# Rectifire__PFC__Evaluation_Board.net
KiCad netlist of a schematic drawn in Altium Designer
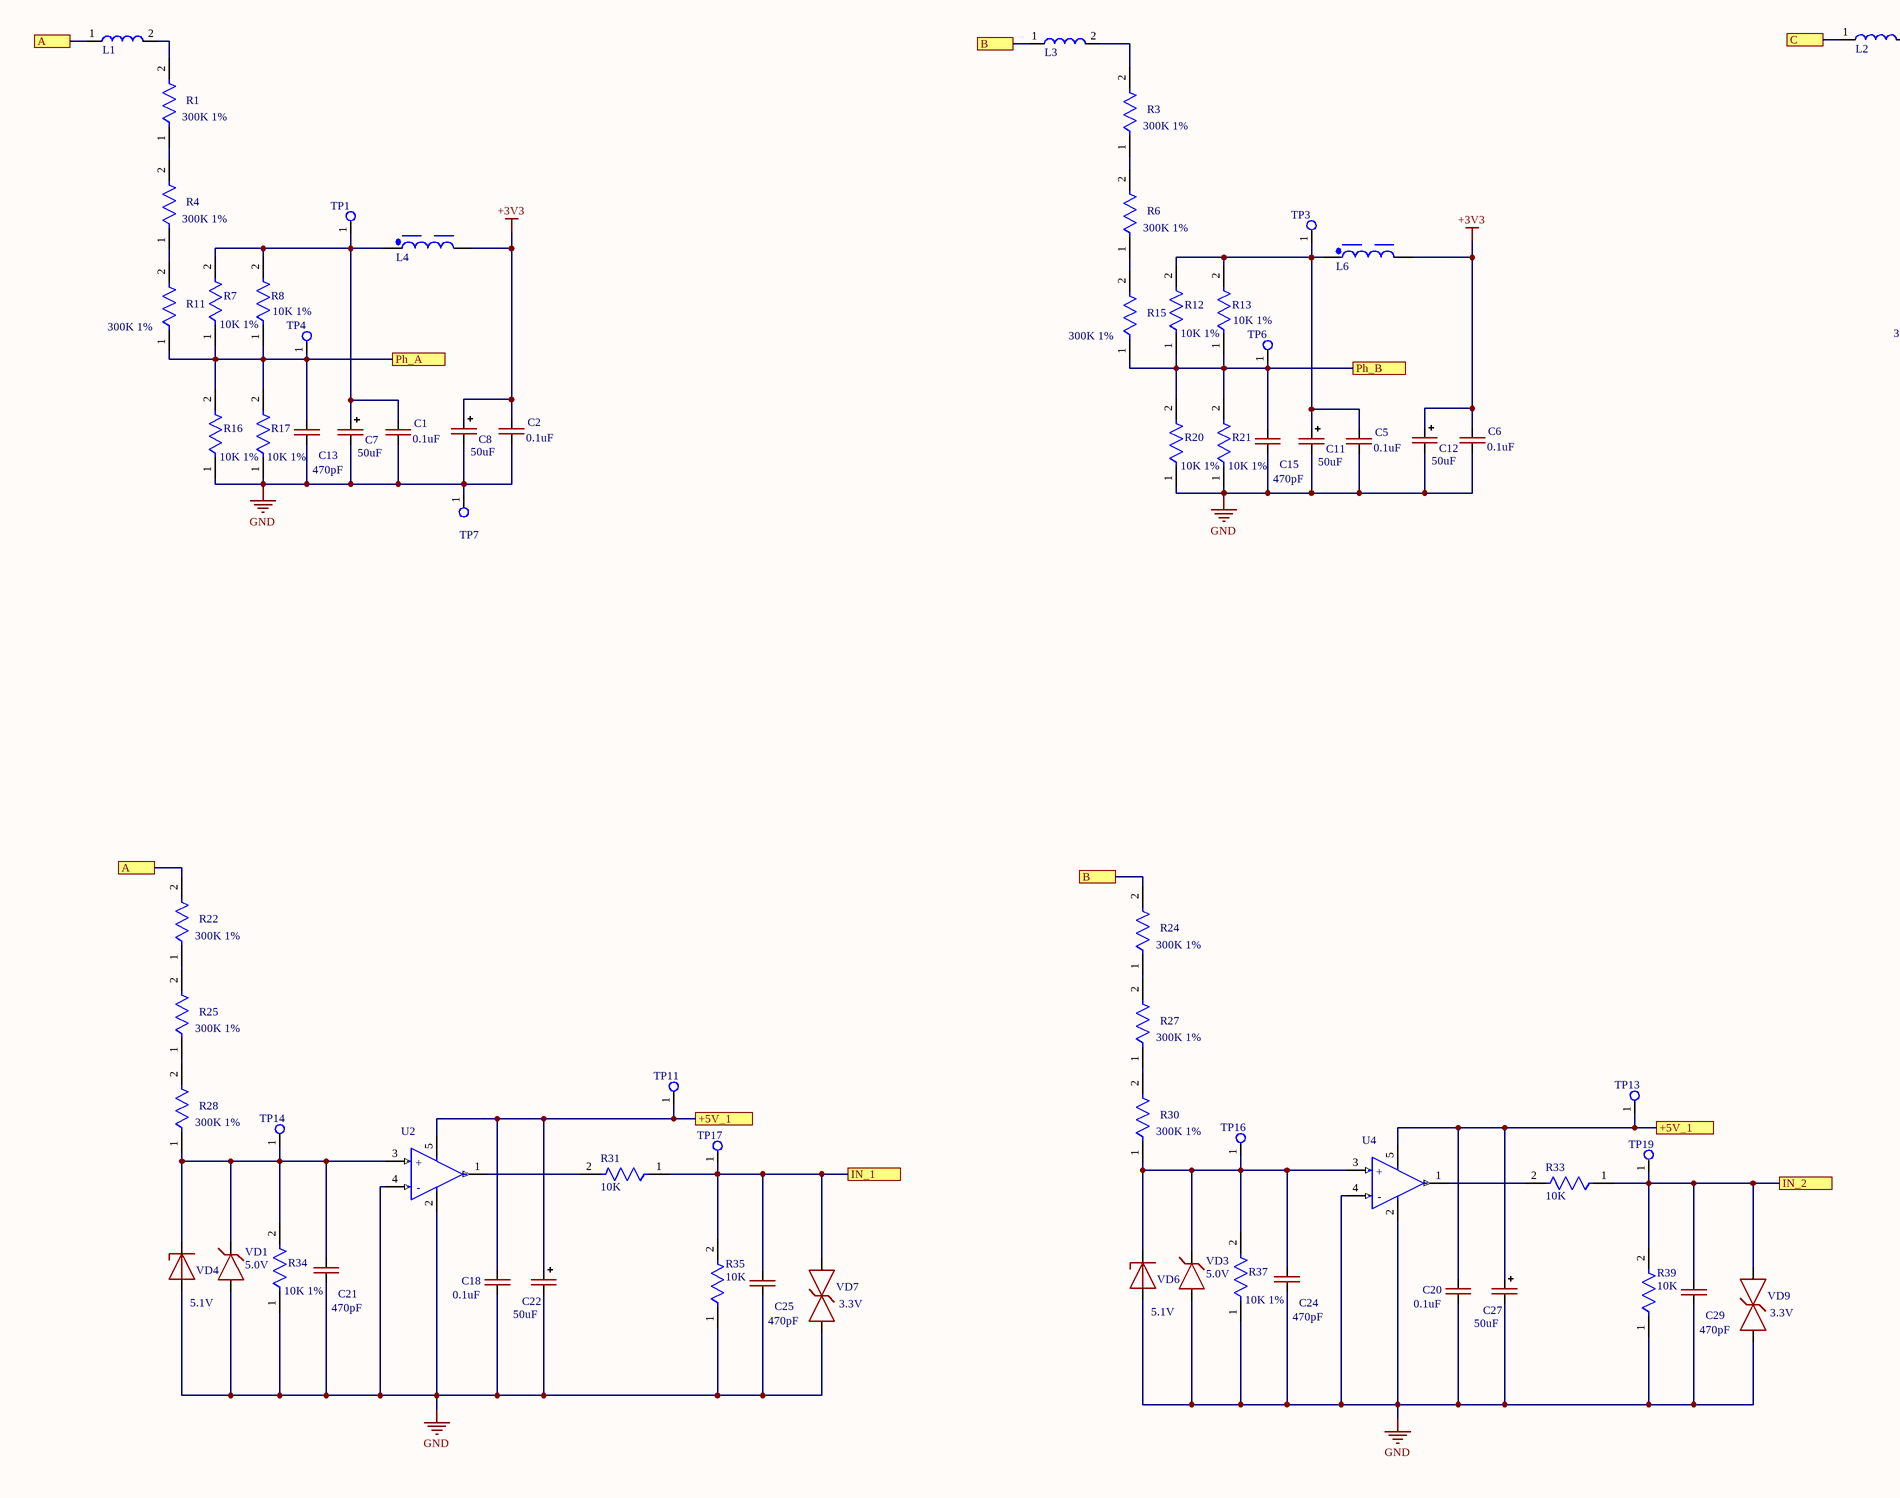
[diagram p0: Rectifire_(PFC)_Evaluation_Board.SchDoc, left]
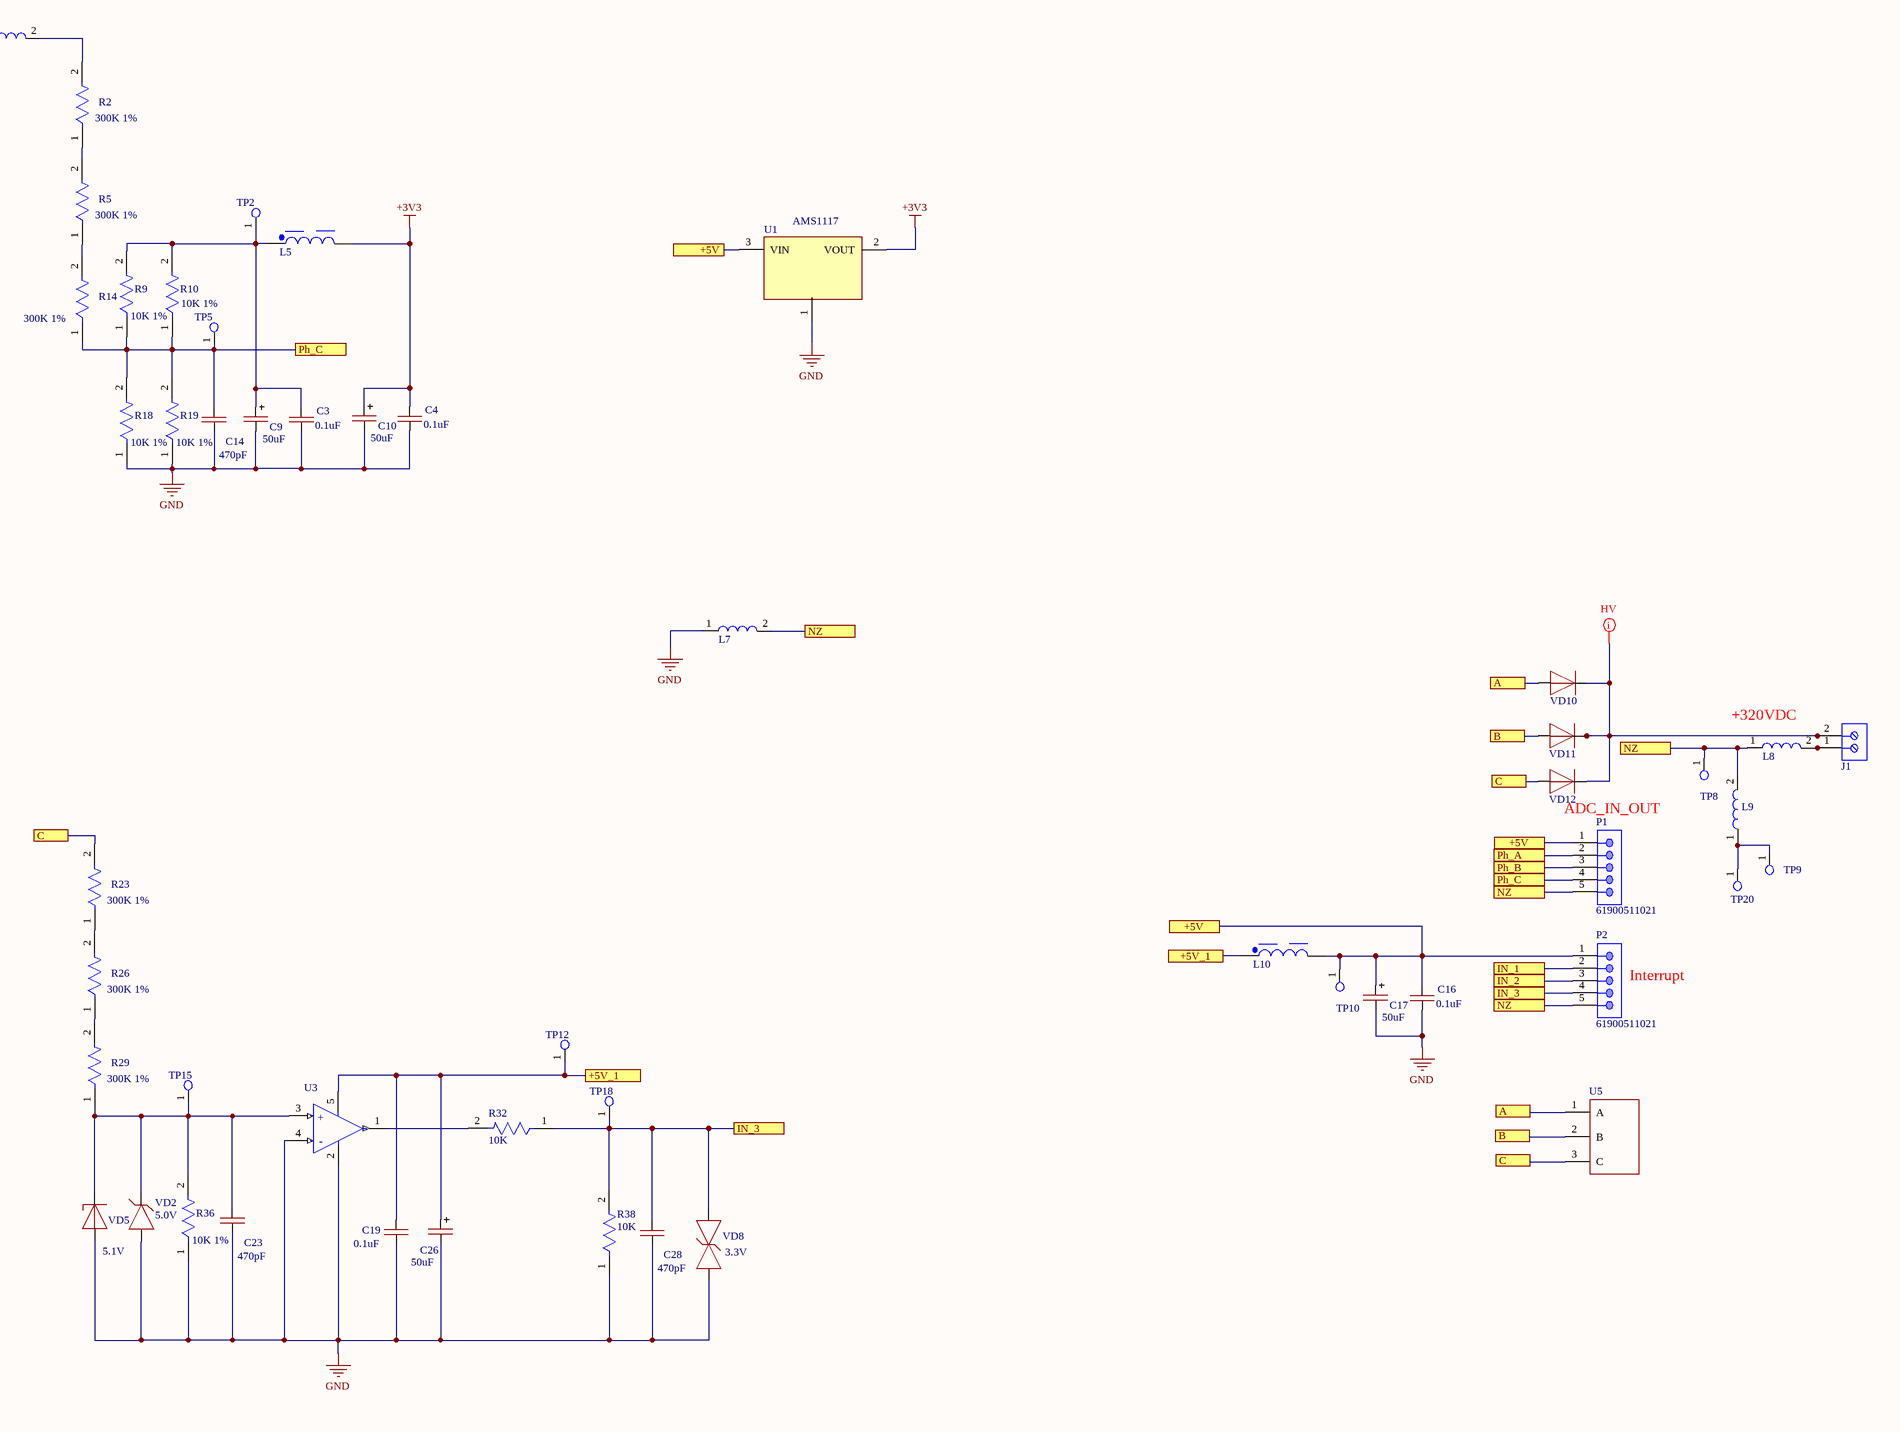
[diagram p1: Rectifire_(PFC)_Evaluation_Board.SchDoc, right]

(export (version "E")
  (design (tool "Eeschema 10.0.6"))
  (components
    (comp (ref "C1")
      (value "0.1uF")
      (footprint "CAP-0805")
      (libsource (lib "PASSIVE_COMPONENTS") (part "CAP-NON-POLAR"))
    )
    (comp (ref "C2")
      (value "0.1uF")
      (footprint "CAP-0805")
      (libsource (lib "PASSIVE_COMPONENTS") (part "CAP-NON-POLAR"))
    )
    (comp (ref "C3")
      (value "0.1uF")
      (footprint "CAP-0805")
      (libsource (lib "PASSIVE_COMPONENTS") (part "CAP-NON-POLAR"))
    )
    (comp (ref "C4")
      (value "0.1uF")
      (footprint "CAP-0805")
      (libsource (lib "PASSIVE_COMPONENTS") (part "CAP-NON-POLAR"))
    )
    (comp (ref "C5")
      (value "0.1uF")
      (footprint "CAP-0805")
      (libsource (lib "PASSIVE_COMPONENTS") (part "CAP-NON-POLAR"))
    )
    (comp (ref "C6")
      (value "0.1uF")
      (footprint "CAP-0805")
      (libsource (lib "PASSIVE_COMPONENTS") (part "CAP-NON-POLAR"))
    )
    (comp (ref "C7")
      (value "50uF")
      (footprint "CAP-TAN-D")
      (libsource (lib "PASSIVE_COMPONENTS") (part "CAP-POLAR"))
    )
    (comp (ref "C8")
      (value "50uF")
      (footprint "CAP-TAN-D")
      (libsource (lib "PASSIVE_COMPONENTS") (part "CAP-POLAR"))
    )
    (comp (ref "C9")
      (value "50uF")
      (footprint "CAP-TAN-D")
      (libsource (lib "PASSIVE_COMPONENTS") (part "CAP-POLAR"))
    )
    (comp (ref "C10")
      (value "50uF")
      (footprint "CAP-TAN-D")
      (libsource (lib "PASSIVE_COMPONENTS") (part "CAP-POLAR"))
    )
    (comp (ref "C11")
      (value "50uF")
      (footprint "CAP-TAN-D")
      (libsource (lib "PASSIVE_COMPONENTS") (part "CAP-POLAR"))
    )
    (comp (ref "C12")
      (value "50uF")
      (footprint "CAP-TAN-D")
      (libsource (lib "PASSIVE_COMPONENTS") (part "CAP-POLAR"))
    )
    (comp (ref "C13")
      (value "470pF")
      (footprint "CAP-0805")
      (libsource (lib "PASSIVE_COMPONENTS") (part "CAP-NON-POLAR"))
    )
    (comp (ref "C14")
      (value "470pF")
      (footprint "CAP-0805")
      (libsource (lib "PASSIVE_COMPONENTS") (part "CAP-NON-POLAR"))
    )
    (comp (ref "C15")
      (value "470pF")
      (footprint "CAP-0805")
      (libsource (lib "PASSIVE_COMPONENTS") (part "CAP-NON-POLAR"))
    )
    (comp (ref "C16")
      (value "0.1uF")
      (footprint "CAP-0805")
      (libsource (lib "PASSIVE_COMPONENTS") (part "CAP-NON-POLAR"))
    )
    (comp (ref "C17")
      (value "50uF")
      (footprint "CAP-TAN-D")
      (libsource (lib "PASSIVE_COMPONENTS") (part "CAP-POLAR"))
    )
    (comp (ref "C18")
      (value "0.1uF")
      (footprint "CAP-0805")
      (libsource (lib "PASSIVE_COMPONENTS") (part "CAP-NON-POLAR"))
    )
    (comp (ref "C19")
      (value "0.1uF")
      (footprint "CAP-0805")
      (libsource (lib "PASSIVE_COMPONENTS") (part "CAP-NON-POLAR"))
    )
    (comp (ref "C20")
      (value "0.1uF")
      (footprint "CAP-0805")
      (libsource (lib "PASSIVE_COMPONENTS") (part "CAP-NON-POLAR"))
    )
    (comp (ref "C21")
      (value "470pF")
      (footprint "CAP-0805")
      (libsource (lib "PASSIVE_COMPONENTS") (part "CAP-NON-POLAR"))
    )
    (comp (ref "C22")
      (value "50uF")
      (footprint "CAP-TAN-D")
      (libsource (lib "PASSIVE_COMPONENTS") (part "CAP-POLAR"))
    )
    (comp (ref "C23")
      (value "470pF")
      (footprint "CAP-0805")
      (libsource (lib "PASSIVE_COMPONENTS") (part "CAP-NON-POLAR"))
    )
    (comp (ref "C24")
      (value "470pF")
      (footprint "CAP-0805")
      (libsource (lib "PASSIVE_COMPONENTS") (part "CAP-NON-POLAR"))
    )
    (comp (ref "C25")
      (value "470pF")
      (footprint "CAP-0805")
      (libsource (lib "PASSIVE_COMPONENTS") (part "CAP-NON-POLAR"))
    )
    (comp (ref "C26")
      (value "50uF")
      (footprint "CAP-TAN-D")
      (libsource (lib "PASSIVE_COMPONENTS") (part "CAP-POLAR"))
    )
    (comp (ref "C27")
      (value "50uF")
      (footprint "CAP-TAN-D")
      (libsource (lib "PASSIVE_COMPONENTS") (part "CAP-POLAR"))
    )
    (comp (ref "C28")
      (value "470pF")
      (footprint "CAP-0805")
      (libsource (lib "PASSIVE_COMPONENTS") (part "CAP-NON-POLAR"))
    )
    (comp (ref "C29")
      (value "470pF")
      (footprint "CAP-0805")
      (libsource (lib "PASSIVE_COMPONENTS") (part "CAP-NON-POLAR"))
    )
    (comp (ref "J1")
      (value "691101710002")
      (footprint "691101710002")
      (description "WR-TBL Series 101 Horizontal Entry Modular, THT, pitch 5mm, 2p")
      (fields (field (name "MANUFACTURER") "Wurth Elektronik"))
      (libsource (lib "Altium_WR-TBL (rev23f)") (part "691101710002"))
    )
    (comp (ref "L1") (value "Coil") (footprint "NR4030") (libsource (lib "Transformers") (part "Coil")))
    (comp (ref "L2") (value "Coil") (footprint "NR4030") (libsource (lib "Transformers") (part "Coil")))
    (comp (ref "L3") (value "Coil") (footprint "NR4030") (libsource (lib "Transformers") (part "Coil")))
    (comp (ref "L4")
      (value "12µH, 1.28A")
      (footprint "WE-PD2_4532")
      (description "WE-PD2 SMT Power Inductor, size 4532, 12µH, 1.28A, 0.21Ω")
      (fields
        (field (name "MANUFACTURER PART NUMBER") "744773112")
        (field (name "MANUFACTURER") "Wurth Elektronik")
      )
      (libsource (lib "WE-PD2 (rev22d)") (part "744773112"))
    )
    (comp (ref "L5")
      (value "12µH, 1.28A")
      (footprint "WE-PD2_4532")
      (description "WE-PD2 SMT Power Inductor, size 4532, 12µH, 1.28A, 0.21Ω")
      (fields
        (field (name "MANUFACTURER PART NUMBER") "744773112")
        (field (name "MANUFACTURER") "Wurth Elektronik")
      )
      (libsource (lib "WE-PD2 (rev22d)") (part "744773112"))
    )
    (comp (ref "L6")
      (value "12µH, 1.28A")
      (footprint "WE-PD2_4532")
      (description "WE-PD2 SMT Power Inductor, size 4532, 12µH, 1.28A, 0.21Ω")
      (fields
        (field (name "MANUFACTURER PART NUMBER") "744773112")
        (field (name "MANUFACTURER") "Wurth Elektronik")
      )
      (libsource (lib "WE-PD2 (rev22d)") (part "744773112"))
    )
    (comp (ref "L7") (value "Coil") (footprint "NR4030") (libsource (lib "Transformers") (part "Coil")))
    (comp (ref "L8") (value "Coil") (footprint "NR4030") (libsource (lib "Transformers") (part "Coil")))
    (comp (ref "L9") (value "Coil") (footprint "NR4030") (libsource (lib "Transformers") (part "Coil")))
    (comp (ref "L10")
      (value "12µH, 1.28A")
      (footprint "WE-PD2_4532")
      (description "WE-PD2 SMT Power Inductor, size 4532, 12µH, 1.28A, 0.21Ω")
      (fields
        (field (name "MANUFACTURER PART NUMBER") "744773112")
        (field (name "MANUFACTURER") "Wurth Elektronik")
      )
      (libsource (lib "WE-PD2 (rev22d)") (part "744773112"))
    )
    (comp (ref "P1")
      (value "61900511021")
      (footprint "61900511021")
      (description "WR-WTB THT Male Left Angled Bottom Locking Header, pitch 2.54mm, 5p")
      (fields (field (name "PUBLISHER") "Wurth Elektronik"))
      (libsource (lib "Altium_WR-WTB (rev20a)") (part "61900511021"))
    )
    (comp (ref "P2")
      (value "61900511021")
      (footprint "61900511021")
      (description "WR-WTB THT Male Left Angled Bottom Locking Header, pitch 2.54mm, 5p")
      (fields (field (name "PUBLISHER") "Wurth Elektronik"))
      (libsource (lib "Altium_WR-WTB (rev20a)") (part "61900511021"))
    )
    (comp (ref "R1")
      (value "300K 1%")
      (footprint "RES-1206")
      (description "300K")
      (libsource (lib "PASSIVE_COMPONENTS") (part "RES-CONST"))
    )
    (comp (ref "R2")
      (value "300K 1%")
      (footprint "RES-1206")
      (description "300K")
      (libsource (lib "PASSIVE_COMPONENTS") (part "RES-CONST"))
    )
    (comp (ref "R3")
      (value "300K 1%")
      (footprint "RES-1206")
      (description "300K")
      (libsource (lib "PASSIVE_COMPONENTS") (part "RES-CONST"))
    )
    (comp (ref "R4")
      (value "300K 1%")
      (footprint "RES-1206")
      (description "300K")
      (libsource (lib "PASSIVE_COMPONENTS") (part "RES-CONST"))
    )
    (comp (ref "R5")
      (value "300K 1%")
      (footprint "RES-1206")
      (description "300K")
      (libsource (lib "PASSIVE_COMPONENTS") (part "RES-CONST"))
    )
    (comp (ref "R6")
      (value "300K 1%")
      (footprint "RES-1206")
      (description "300K")
      (libsource (lib "PASSIVE_COMPONENTS") (part "RES-CONST"))
    )
    (comp (ref "R7")
      (value "10K 1%")
      (footprint "RES-1206")
      (libsource (lib "PASSIVE_COMPONENTS") (part "RES-CONST"))
    )
    (comp (ref "R8")
      (value "10K 1%")
      (footprint "RES-1206")
      (description "10K")
      (libsource (lib "PASSIVE_COMPONENTS") (part "RES-CONST"))
    )
    (comp (ref "R9")
      (value "10K 1%")
      (footprint "RES-1206")
      (libsource (lib "PASSIVE_COMPONENTS") (part "RES-CONST"))
    )
    (comp (ref "R10")
      (value "10K 1%")
      (footprint "RES-1206")
      (description "10K")
      (libsource (lib "PASSIVE_COMPONENTS") (part "RES-CONST"))
    )
    (comp (ref "R11")
      (value "300K 1%")
      (footprint "RES-1206")
      (description "300K")
      (libsource (lib "PASSIVE_COMPONENTS") (part "RES-CONST"))
    )
    (comp (ref "R12")
      (value "10K 1%")
      (footprint "RES-1206")
      (libsource (lib "PASSIVE_COMPONENTS") (part "RES-CONST"))
    )
    (comp (ref "R13")
      (value "10K 1%")
      (footprint "RES-1206")
      (description "10K")
      (libsource (lib "PASSIVE_COMPONENTS") (part "RES-CONST"))
    )
    (comp (ref "R14")
      (value "300K 1%")
      (footprint "RES-1206")
      (description "300K")
      (libsource (lib "PASSIVE_COMPONENTS") (part "RES-CONST"))
    )
    (comp (ref "R15")
      (value "300K 1%")
      (footprint "RES-1206")
      (description "300K")
      (libsource (lib "PASSIVE_COMPONENTS") (part "RES-CONST"))
    )
    (comp (ref "R16")
      (value "10K 1%")
      (footprint "RES-1206")
      (description "10K")
      (libsource (lib "PASSIVE_COMPONENTS") (part "RES-CONST"))
    )
    (comp (ref "R17")
      (value "10K 1%")
      (footprint "RES-1206")
      (description "10K")
      (libsource (lib "PASSIVE_COMPONENTS") (part "RES-CONST"))
    )
    (comp (ref "R18")
      (value "10K 1%")
      (footprint "RES-1206")
      (description "10K")
      (libsource (lib "PASSIVE_COMPONENTS") (part "RES-CONST"))
    )
    (comp (ref "R19")
      (value "10K 1%")
      (footprint "RES-1206")
      (description "10K")
      (libsource (lib "PASSIVE_COMPONENTS") (part "RES-CONST"))
    )
    (comp (ref "R20")
      (value "10K 1%")
      (footprint "RES-1206")
      (description "10K")
      (libsource (lib "PASSIVE_COMPONENTS") (part "RES-CONST"))
    )
    (comp (ref "R21")
      (value "10K 1%")
      (footprint "RES-1206")
      (description "10K")
      (libsource (lib "PASSIVE_COMPONENTS") (part "RES-CONST"))
    )
    (comp (ref "R22")
      (value "300K 1%")
      (footprint "RES-1206")
      (description "300K")
      (libsource (lib "PASSIVE_COMPONENTS") (part "RES-CONST"))
    )
    (comp (ref "R23")
      (value "300K 1%")
      (footprint "RES-1206")
      (description "300K")
      (libsource (lib "PASSIVE_COMPONENTS") (part "RES-CONST"))
    )
    (comp (ref "R24")
      (value "300K 1%")
      (footprint "RES-1206")
      (description "300K")
      (libsource (lib "PASSIVE_COMPONENTS") (part "RES-CONST"))
    )
    (comp (ref "R25")
      (value "300K 1%")
      (footprint "RES-1206")
      (description "300K")
      (libsource (lib "PASSIVE_COMPONENTS") (part "RES-CONST"))
    )
    (comp (ref "R26")
      (value "300K 1%")
      (footprint "RES-1206")
      (description "300K")
      (libsource (lib "PASSIVE_COMPONENTS") (part "RES-CONST"))
    )
    (comp (ref "R27")
      (value "300K 1%")
      (footprint "RES-1206")
      (description "300K")
      (libsource (lib "PASSIVE_COMPONENTS") (part "RES-CONST"))
    )
    (comp (ref "R28")
      (value "300K 1%")
      (footprint "RES-1206")
      (description "300K")
      (libsource (lib "PASSIVE_COMPONENTS") (part "RES-CONST"))
    )
    (comp (ref "R29")
      (value "300K 1%")
      (footprint "RES-1206")
      (description "300K")
      (libsource (lib "PASSIVE_COMPONENTS") (part "RES-CONST"))
    )
    (comp (ref "R30")
      (value "300K 1%")
      (footprint "RES-1206")
      (description "300K")
      (libsource (lib "PASSIVE_COMPONENTS") (part "RES-CONST"))
    )
    (comp (ref "R31")
      (value "10K")
      (footprint "RES-0805")
      (libsource (lib "PASSIVE_COMPONENTS") (part "RES-CONST"))
    )
    (comp (ref "R32")
      (value "10K")
      (footprint "RES-0805")
      (libsource (lib "PASSIVE_COMPONENTS") (part "RES-CONST"))
    )
    (comp (ref "R33")
      (value "10K")
      (footprint "RES-0805")
      (libsource (lib "PASSIVE_COMPONENTS") (part "RES-CONST"))
    )
    (comp (ref "R34")
      (value "10K 1%")
      (footprint "RES-1206")
      (libsource (lib "PASSIVE_COMPONENTS") (part "RES-CONST"))
    )
    (comp (ref "R35")
      (value "10K")
      (footprint "RES-0805")
      (libsource (lib "PASSIVE_COMPONENTS") (part "RES-CONST"))
    )
    (comp (ref "R36")
      (value "10K 1%")
      (footprint "RES-1206")
      (libsource (lib "PASSIVE_COMPONENTS") (part "RES-CONST"))
    )
    (comp (ref "R37")
      (value "10K 1%")
      (footprint "RES-1206")
      (libsource (lib "PASSIVE_COMPONENTS") (part "RES-CONST"))
    )
    (comp (ref "R38")
      (value "10K")
      (footprint "RES-0805")
      (libsource (lib "PASSIVE_COMPONENTS") (part "RES-CONST"))
    )
    (comp (ref "R39")
      (value "10K")
      (footprint "RES-0805")
      (libsource (lib "PASSIVE_COMPONENTS") (part "RES-CONST"))
    )
    (comp (ref "TP1")
      (value "Test_Point_PCB")
      (footprint "Test_Point")
      (description "Test_Point")
      (libsource (lib "Connectors") (part "TP_PCB?"))
    )
    (comp (ref "TP2")
      (value "Test_Point_PCB")
      (footprint "Test_Point")
      (description "Test_Point")
      (libsource (lib "Connectors") (part "TP_PCB?"))
    )
    (comp (ref "TP3")
      (value "Test_Point_PCB")
      (footprint "Test_Point")
      (description "Test_Point")
      (libsource (lib "Connectors") (part "TP_PCB?"))
    )
    (comp (ref "TP4")
      (value "Test_Point_PCB")
      (footprint "Test_Point")
      (description "Test_Point")
      (libsource (lib "Connectors") (part "TP_PCB?"))
    )
    (comp (ref "TP5")
      (value "Test_Point_PCB")
      (footprint "Test_Point")
      (description "Test_Point")
      (libsource (lib "Connectors") (part "TP_PCB?"))
    )
    (comp (ref "TP6")
      (value "Test_Point_PCB")
      (footprint "Test_Point")
      (description "Test_Point")
      (libsource (lib "Connectors") (part "TP_PCB?"))
    )
    (comp (ref "TP7")
      (value "Test_Point_PCB")
      (footprint "Pin_Test_Point(Pink)")
      (description "Test_Point")
      (libsource (lib "Connectors") (part "TP_PCB?"))
    )
    (comp (ref "TP8")
      (value "Test_Point_PCB")
      (footprint "Pin_Test_Point(Pink)")
      (description "Test_Point")
      (libsource (lib "Connectors") (part "TP_PCB?"))
    )
    (comp (ref "TP9")
      (value "Test_Point_PCB")
      (footprint "Pin_Test_Point(Pink)")
      (description "Test_Point")
      (libsource (lib "Connectors") (part "TP_PCB?"))
    )
    (comp (ref "TP10")
      (value "Test_Point_PCB")
      (footprint "Test_Point")
      (description "Test_Point")
      (libsource (lib "Connectors") (part "TP_PCB?"))
    )
    (comp (ref "TP11")
      (value "Test_Point_PCB")
      (footprint "Test_Point")
      (description "Test_Point")
      (libsource (lib "Connectors") (part "TP_PCB?"))
    )
    (comp (ref "TP12")
      (value "Test_Point_PCB")
      (footprint "Test_Point")
      (description "Test_Point")
      (libsource (lib "Connectors") (part "TP_PCB?"))
    )
    (comp (ref "TP13")
      (value "Test_Point_PCB")
      (footprint "Test_Point")
      (description "Test_Point")
      (libsource (lib "Connectors") (part "TP_PCB?"))
    )
    (comp (ref "TP14")
      (value "Test_Point_PCB")
      (footprint "Test_Point")
      (description "Test_Point")
      (libsource (lib "Connectors") (part "TP_PCB?"))
    )
    (comp (ref "TP15")
      (value "Test_Point_PCB")
      (footprint "Test_Point")
      (description "Test_Point")
      (libsource (lib "Connectors") (part "TP_PCB?"))
    )
    (comp (ref "TP16")
      (value "Test_Point_PCB")
      (footprint "Test_Point")
      (description "Test_Point")
      (libsource (lib "Connectors") (part "TP_PCB?"))
    )
    (comp (ref "TP17")
      (value "Test_Point_PCB")
      (footprint "Test_Point")
      (description "Test_Point")
      (libsource (lib "Connectors") (part "TP_PCB?"))
    )
    (comp (ref "TP18")
      (value "Test_Point_PCB")
      (footprint "Test_Point")
      (description "Test_Point")
      (libsource (lib "Connectors") (part "TP_PCB?"))
    )
    (comp (ref "TP19")
      (value "Test_Point_PCB")
      (footprint "Test_Point")
      (description "Test_Point")
      (libsource (lib "Connectors") (part "TP_PCB?"))
    )
    (comp (ref "TP20")
      (value "Test_Point_PCB")
      (footprint "Test_Point")
      (description "Test_Point")
      (libsource (lib "Connectors") (part "TP_PCB?"))
    )
    (comp (ref "U1")
      (value "AMS1117")
      (footprint "SOT-89")
      (libsource (lib "Integrated_Circuts") (part "AMS1117"))
    )
    (comp (ref "U2")
      (value "~")
      (footprint "SOT-23-5")
      (description "IC OPAMP GP 1 CIRCUIT SOT23-5")
      (fields (field (name "VOLTAGE") "6V"))
      (libsource (lib "Integrated_Circuts") (part "MCP6001T"))
    )
    (comp (ref "U3")
      (value "~")
      (footprint "SOT-23-5")
      (description "IC OPAMP GP 1 CIRCUIT SOT23-5")
      (fields (field (name "VOLTAGE") "6V"))
      (libsource (lib "Integrated_Circuts") (part "MCP6001T"))
    )
    (comp (ref "U4")
      (value "~")
      (footprint "SOT-23-5")
      (description "IC OPAMP GP 1 CIRCUIT SOT23-5")
      (fields (field (name "VOLTAGE") "6V"))
      (libsource (lib "Integrated_Circuts") (part "MCP6001T"))
    )
    (comp (ref "U5") (value "~") (footprint "MDS100") (libsource (lib "MDS100") (part "MDS100")))
    (comp (ref "VD1") (value "5.0V") (footprint "SOD-323") (libsource (lib "Diodes") (part "SMBJ15A")))
    (comp (ref "VD2") (value "5.0V") (footprint "DO-214AA") (libsource (lib "Diodes") (part "SMBJ15A")))
    (comp (ref "VD3") (value "5.0V") (footprint "SOD-323") (libsource (lib "Diodes") (part "SMBJ15A")))
    (comp (ref "VD4") (value "5.1V") (footprint "DIOD-SOD123-2_V") (libsource (lib "Diodes") (part "ZENER")))
    (comp (ref "VD5") (value "5.1V") (footprint "DIOD-SOD123-2_V") (libsource (lib "Diodes") (part "ZENER")))
    (comp (ref "VD6") (value "5.1V") (footprint "DIOD-SOD123-2_V") (libsource (lib "Diodes") (part "ZENER")))
    (comp (ref "VD7") (value "3.3V") (footprint "DO-214AA") (libsource (lib "Diodes") (part "Suppressor")))
    (comp (ref "VD8") (value "3.3V") (footprint "DO-214AA") (libsource (lib "Diodes") (part "Suppressor")))
    (comp (ref "VD9") (value "3.3V") (footprint "DO-214AA") (libsource (lib "Diodes") (part "Suppressor")))
    (comp (ref "VD10") (value "DIODE") (footprint "DO-214AB") (libsource (lib "S3M") (part "DIODE")))
    (comp (ref "VD11") (value "DIODE") (footprint "DO-214AB") (libsource (lib "S3M") (part "DIODE")))
    (comp (ref "VD12") (value "DIODE") (footprint "DO-214AB") (libsource (lib "S3M") (part "DIODE")))
  )
  (nets
    (net (code "1") (name "+3V3") (class "Default")
      (node (ref "C10") (pin "1") (pinfunction "+_1") (pintype "passive"))
      (node (ref "C12") (pin "1") (pinfunction "+_1") (pintype "passive"))
      (node (ref "C2") (pin "2") (pinfunction "2_2") (pintype "passive"))
      (node (ref "C4") (pin "2") (pinfunction "2_2") (pintype "passive"))
      (node (ref "C6") (pin "2") (pinfunction "2_2") (pintype "passive"))
      (node (ref "C8") (pin "1") (pinfunction "+_1") (pintype "passive"))
      (node (ref "L4") (pin "2") (pinfunction "2_2") (pintype "passive"))
      (node (ref "L5") (pin "2") (pinfunction "2_2") (pintype "passive"))
      (node (ref "L6") (pin "2") (pinfunction "2_2") (pintype "passive"))
      (node (ref "U1") (pin "2") (pinfunction "VOUT_2") (pintype "passive"))
    )
    (net (code "2") (name "/+5V") (class "Default")
      (node (ref "C16") (pin "2") (pinfunction "2_2") (pintype "passive"))
      (node (ref "C17") (pin "1") (pinfunction "+_1") (pintype "passive"))
      (node (ref "L10") (pin "2") (pinfunction "2_2") (pintype "passive"))
      (node (ref "P1") (pin "1") (pinfunction "1_1") (pintype "passive"))
      (node (ref "P2") (pin "1") (pinfunction "1_1") (pintype "passive"))
      (node (ref "TP10") (pin "1") (pinfunction "G9_1") (pintype "passive"))
      (node (ref "U1") (pin "3") (pinfunction "VIN_3") (pintype "power_in"))
    )
    (net (code "3") (name "/+5V_1") (class "Default")
      (node (ref "C18") (pin "2") (pinfunction "2_2") (pintype "passive"))
      (node (ref "C19") (pin "2") (pinfunction "2_2") (pintype "passive"))
      (node (ref "C20") (pin "2") (pinfunction "2_2") (pintype "passive"))
      (node (ref "C22") (pin "1") (pinfunction "+_1") (pintype "passive"))
      (node (ref "C26") (pin "1") (pinfunction "+_1") (pintype "passive"))
      (node (ref "C27") (pin "1") (pinfunction "+_1") (pintype "passive"))
      (node (ref "L10") (pin "1") (pinfunction "1_1") (pintype "passive"))
      (node (ref "TP11") (pin "1") (pinfunction "G9_1") (pintype "passive"))
      (node (ref "TP12") (pin "1") (pinfunction "G9_1") (pintype "passive"))
      (node (ref "TP13") (pin "1") (pinfunction "G9_1") (pintype "passive"))
      (node (ref "U2") (pin "5") (pinfunction "VDD_5") (pintype "power_in"))
      (node (ref "U3") (pin "5") (pinfunction "VDD_5") (pintype "power_in"))
      (node (ref "U4") (pin "5") (pinfunction "VDD_5") (pintype "power_in"))
    )
    (net (code "4") (name "/A") (class "Default")
      (node (ref "L1") (pin "1") (pinfunction "1_1") (pintype "passive"))
      (node (ref "R22") (pin "2") (pinfunction "2_2") (pintype "passive"))
      (node (ref "U5") (pin "1") (pinfunction "A_1") (pintype "tri_state"))
      (node (ref "VD10") (pin "2") (pinfunction "A_2") (pintype "passive"))
    )
    (net (code "5") (name "/B") (class "Default")
      (node (ref "L3") (pin "1") (pinfunction "1_1") (pintype "passive"))
      (node (ref "R24") (pin "2") (pinfunction "2_2") (pintype "passive"))
      (node (ref "U5") (pin "2") (pinfunction "B_2") (pintype "tri_state"))
      (node (ref "VD11") (pin "2") (pinfunction "A_2") (pintype "passive"))
    )
    (net (code "6") (name "/C") (class "Default")
      (node (ref "L2") (pin "1") (pinfunction "1_1") (pintype "passive"))
      (node (ref "R23") (pin "2") (pinfunction "2_2") (pintype "passive"))
      (node (ref "U5") (pin "3") (pinfunction "C_3") (pintype "tri_state"))
      (node (ref "VD12") (pin "2") (pinfunction "A_2") (pintype "passive"))
    )
    (net (code "7") (name "/IN_1") (class "Default")
      (node (ref "C25") (pin "2") (pinfunction "2_2") (pintype "passive"))
      (node (ref "P2") (pin "2") (pinfunction "2_2") (pintype "passive"))
      (node (ref "R31") (pin "1") (pinfunction "1_1") (pintype "passive"))
      (node (ref "R35") (pin "2") (pinfunction "2_2") (pintype "passive"))
      (node (ref "TP17") (pin "1") (pinfunction "G9_1") (pintype "passive"))
      (node (ref "VD7") (pin "2") (pinfunction "A_2") (pintype "passive"))
    )
    (net (code "8") (name "/IN_2") (class "Default")
      (node (ref "C29") (pin "2") (pinfunction "2_2") (pintype "passive"))
      (node (ref "P2") (pin "3") (pinfunction "3_3") (pintype "passive"))
      (node (ref "R33") (pin "1") (pinfunction "1_1") (pintype "passive"))
      (node (ref "R39") (pin "2") (pinfunction "2_2") (pintype "passive"))
      (node (ref "TP19") (pin "1") (pinfunction "G9_1") (pintype "passive"))
      (node (ref "VD9") (pin "2") (pinfunction "A_2") (pintype "passive"))
    )
    (net (code "9") (name "/IN_3") (class "Default")
      (node (ref "C28") (pin "2") (pinfunction "2_2") (pintype "passive"))
      (node (ref "P2") (pin "4") (pinfunction "4_4") (pintype "passive"))
      (node (ref "R32") (pin "1") (pinfunction "1_1") (pintype "passive"))
      (node (ref "R38") (pin "2") (pinfunction "2_2") (pintype "passive"))
      (node (ref "TP18") (pin "1") (pinfunction "G9_1") (pintype "passive"))
      (node (ref "VD8") (pin "2") (pinfunction "A_2") (pintype "passive"))
    )
    (net (code "10") (name "/NZ") (class "Default")
      (node (ref "L7") (pin "2") (pinfunction "2_2") (pintype "passive"))
      (node (ref "L8") (pin "1") (pinfunction "1_1") (pintype "passive"))
      (node (ref "L9") (pin "2") (pinfunction "2_2") (pintype "passive"))
      (node (ref "P1") (pin "5") (pinfunction "5_5") (pintype "passive"))
      (node (ref "P2") (pin "5") (pinfunction "5_5") (pintype "passive"))
      (node (ref "TP8") (pin "1") (pinfunction "G9_1") (pintype "passive"))
    )
    (net (code "11") (name "/Ph_A") (class "Default")
      (node (ref "C13") (pin "2") (pinfunction "2_2") (pintype "passive"))
      (node (ref "P1") (pin "2") (pinfunction "2_2") (pintype "passive"))
      (node (ref "R11") (pin "1") (pinfunction "1_1") (pintype "passive"))
      (node (ref "R16") (pin "2") (pinfunction "2_2") (pintype "passive"))
      (node (ref "R17") (pin "2") (pinfunction "2_2") (pintype "passive"))
      (node (ref "R7") (pin "1") (pinfunction "1_1") (pintype "passive"))
      (node (ref "R8") (pin "1") (pinfunction "1_1") (pintype "passive"))
      (node (ref "TP4") (pin "1") (pinfunction "G9_1") (pintype "passive"))
    )
    (net (code "12") (name "/Ph_B") (class "Default")
      (node (ref "C15") (pin "2") (pinfunction "2_2") (pintype "passive"))
      (node (ref "P1") (pin "3") (pinfunction "3_3") (pintype "passive"))
      (node (ref "R12") (pin "1") (pinfunction "1_1") (pintype "passive"))
      (node (ref "R13") (pin "1") (pinfunction "1_1") (pintype "passive"))
      (node (ref "R15") (pin "1") (pinfunction "1_1") (pintype "passive"))
      (node (ref "R20") (pin "2") (pinfunction "2_2") (pintype "passive"))
      (node (ref "R21") (pin "2") (pinfunction "2_2") (pintype "passive"))
      (node (ref "TP6") (pin "1") (pinfunction "G9_1") (pintype "passive"))
    )
    (net (code "13") (name "/Ph_C") (class "Default")
      (node (ref "C14") (pin "2") (pinfunction "2_2") (pintype "passive"))
      (node (ref "P1") (pin "4") (pinfunction "4_4") (pintype "passive"))
      (node (ref "R10") (pin "1") (pinfunction "1_1") (pintype "passive"))
      (node (ref "R14") (pin "1") (pinfunction "1_1") (pintype "passive"))
      (node (ref "R18") (pin "2") (pinfunction "2_2") (pintype "passive"))
      (node (ref "R19") (pin "2") (pinfunction "2_2") (pintype "passive"))
      (node (ref "R9") (pin "1") (pinfunction "1_1") (pintype "passive"))
      (node (ref "TP5") (pin "1") (pinfunction "G9_1") (pintype "passive"))
    )
    (net (code "14") (name "GND") (class "Default")
      (node (ref "C1") (pin "1") (pinfunction "1_1") (pintype "passive"))
      (node (ref "C10") (pin "2") (pinfunction "-_2") (pintype "passive"))
      (node (ref "C11") (pin "2") (pinfunction "-_2") (pintype "passive"))
      (node (ref "C12") (pin "2") (pinfunction "-_2") (pintype "passive"))
      (node (ref "C13") (pin "1") (pinfunction "1_1") (pintype "passive"))
      (node (ref "C14") (pin "1") (pinfunction "1_1") (pintype "passive"))
      (node (ref "C15") (pin "1") (pinfunction "1_1") (pintype "passive"))
      (node (ref "C16") (pin "1") (pinfunction "1_1") (pintype "passive"))
      (node (ref "C17") (pin "2") (pinfunction "-_2") (pintype "passive"))
      (node (ref "C18") (pin "1") (pinfunction "1_1") (pintype "passive"))
      (node (ref "C19") (pin "1") (pinfunction "1_1") (pintype "passive"))
      (node (ref "C2") (pin "1") (pinfunction "1_1") (pintype "passive"))
      (node (ref "C20") (pin "1") (pinfunction "1_1") (pintype "passive"))
      (node (ref "C21") (pin "1") (pinfunction "1_1") (pintype "passive"))
      (node (ref "C22") (pin "2") (pinfunction "-_2") (pintype "passive"))
      (node (ref "C23") (pin "1") (pinfunction "1_1") (pintype "passive"))
      (node (ref "C24") (pin "1") (pinfunction "1_1") (pintype "passive"))
      (node (ref "C25") (pin "1") (pinfunction "1_1") (pintype "passive"))
      (node (ref "C26") (pin "2") (pinfunction "-_2") (pintype "passive"))
      (node (ref "C27") (pin "2") (pinfunction "-_2") (pintype "passive"))
      (node (ref "C28") (pin "1") (pinfunction "1_1") (pintype "passive"))
      (node (ref "C29") (pin "1") (pinfunction "1_1") (pintype "passive"))
      (node (ref "C3") (pin "1") (pinfunction "1_1") (pintype "passive"))
      (node (ref "C4") (pin "1") (pinfunction "1_1") (pintype "passive"))
      (node (ref "C5") (pin "1") (pinfunction "1_1") (pintype "passive"))
      (node (ref "C6") (pin "1") (pinfunction "1_1") (pintype "passive"))
      (node (ref "C7") (pin "2") (pinfunction "-_2") (pintype "passive"))
      (node (ref "C8") (pin "2") (pinfunction "-_2") (pintype "passive"))
      (node (ref "C9") (pin "2") (pinfunction "-_2") (pintype "passive"))
      (node (ref "L7") (pin "1") (pinfunction "1_1") (pintype "passive"))
      (node (ref "R16") (pin "1") (pinfunction "1_1") (pintype "passive"))
      (node (ref "R17") (pin "1") (pinfunction "1_1") (pintype "passive"))
      (node (ref "R18") (pin "1") (pinfunction "1_1") (pintype "passive"))
      (node (ref "R19") (pin "1") (pinfunction "1_1") (pintype "passive"))
      (node (ref "R20") (pin "1") (pinfunction "1_1") (pintype "passive"))
      (node (ref "R21") (pin "1") (pinfunction "1_1") (pintype "passive"))
      (node (ref "R34") (pin "1") (pinfunction "1_1") (pintype "passive"))
      (node (ref "R35") (pin "1") (pinfunction "1_1") (pintype "passive"))
      (node (ref "R36") (pin "1") (pinfunction "1_1") (pintype "passive"))
      (node (ref "R37") (pin "1") (pinfunction "1_1") (pintype "passive"))
      (node (ref "R38") (pin "1") (pinfunction "1_1") (pintype "passive"))
      (node (ref "R39") (pin "1") (pinfunction "1_1") (pintype "passive"))
      (node (ref "TP7") (pin "1") (pinfunction "G9_1") (pintype "passive"))
      (node (ref "U1") (pin "1") (pinfunction "Ground_1") (pintype "power_in"))
      (node (ref "U2") (pin "2") (pinfunction "VSS_2") (pintype "power_in"))
      (node (ref "U2") (pin "4") (pinfunction "VIN-_4") (pintype "input"))
      (node (ref "U3") (pin "2") (pinfunction "VSS_2") (pintype "power_in"))
      (node (ref "U3") (pin "4") (pinfunction "VIN-_4") (pintype "input"))
      (node (ref "U4") (pin "2") (pinfunction "VSS_2") (pintype "power_in"))
      (node (ref "U4") (pin "4") (pinfunction "VIN-_4") (pintype "input"))
      (node (ref "VD1") (pin "1") (pinfunction "A_1") (pintype "passive"))
      (node (ref "VD2") (pin "1") (pinfunction "A_1") (pintype "passive"))
      (node (ref "VD3") (pin "1") (pinfunction "A_1") (pintype "passive"))
      (node (ref "VD4") (pin "2") (pinfunction "A_2") (pintype "passive"))
      (node (ref "VD5") (pin "2") (pinfunction "A_2") (pintype "passive"))
      (node (ref "VD6") (pin "2") (pinfunction "A_2") (pintype "passive"))
      (node (ref "VD7") (pin "1") (pinfunction "C_1") (pintype "passive"))
      (node (ref "VD8") (pin "1") (pinfunction "C_1") (pintype "passive"))
      (node (ref "VD9") (pin "1") (pinfunction "C_1") (pintype "passive"))
    )
    (net (code "15") (name "Net-(C7-+)") (class "Default")
      (node (ref "C1") (pin "2") (pinfunction "2_2") (pintype "passive"))
      (node (ref "C7") (pin "1") (pinfunction "+_1") (pintype "passive"))
      (node (ref "L4") (pin "1") (pinfunction "1_1") (pintype "passive"))
      (node (ref "R7") (pin "2") (pinfunction "2_2") (pintype "passive"))
      (node (ref "R8") (pin "2") (pinfunction "2_2") (pintype "passive"))
      (node (ref "TP1") (pin "1") (pinfunction "G9_1") (pintype "passive"))
    )
    (net (code "16") (name "Net-(C9-+)") (class "Default")
      (node (ref "C3") (pin "2") (pinfunction "2_2") (pintype "passive"))
      (node (ref "C9") (pin "1") (pinfunction "+_1") (pintype "passive"))
      (node (ref "L5") (pin "1") (pinfunction "1_1") (pintype "passive"))
      (node (ref "R10") (pin "2") (pinfunction "2_2") (pintype "passive"))
      (node (ref "R9") (pin "2") (pinfunction "2_2") (pintype "passive"))
      (node (ref "TP2") (pin "1") (pinfunction "G9_1") (pintype "passive"))
    )
    (net (code "17") (name "Net-(C11-+)") (class "Default")
      (node (ref "C11") (pin "1") (pinfunction "+_1") (pintype "passive"))
      (node (ref "C5") (pin "2") (pinfunction "2_2") (pintype "passive"))
      (node (ref "L6") (pin "1") (pinfunction "1_1") (pintype "passive"))
      (node (ref "R12") (pin "2") (pinfunction "2_2") (pintype "passive"))
      (node (ref "R13") (pin "2") (pinfunction "2_2") (pintype "passive"))
      (node (ref "TP3") (pin "1") (pinfunction "G9_1") (pintype "passive"))
    )
    (net (code "18") (name "Net-(J1-Pad1)") (class "Default")
      (node (ref "J1") (pin "1") (pinfunction "1_1") (pintype "passive"))
      (node (ref "L8") (pin "2") (pinfunction "2_2") (pintype "passive"))
    )
    (net (code "19") (name "Net-(L1-Pad2)") (class "Default")
      (node (ref "L1") (pin "2") (pinfunction "2_2") (pintype "passive"))
      (node (ref "R1") (pin "2") (pinfunction "2_2") (pintype "passive"))
    )
    (net (code "20") (name "Net-(L2-Pad2)") (class "Default")
      (node (ref "L2") (pin "2") (pinfunction "2_2") (pintype "passive"))
      (node (ref "R2") (pin "2") (pinfunction "2_2") (pintype "passive"))
    )
    (net (code "21") (name "Net-(L3-Pad2)") (class "Default")
      (node (ref "L3") (pin "2") (pinfunction "2_2") (pintype "passive"))
      (node (ref "R3") (pin "2") (pinfunction "2_2") (pintype "passive"))
    )
    (net (code "22") (name "Net-(R1-Pad1)") (class "Default")
      (node (ref "R1") (pin "1") (pinfunction "1_1") (pintype "passive"))
      (node (ref "R4") (pin "2") (pinfunction "2_2") (pintype "passive"))
    )
    (net (code "23") (name "Net-(R2-Pad1)") (class "Default")
      (node (ref "R2") (pin "1") (pinfunction "1_1") (pintype "passive"))
      (node (ref "R5") (pin "2") (pinfunction "2_2") (pintype "passive"))
    )
    (net (code "24") (name "Net-(R3-Pad1)") (class "Default")
      (node (ref "R3") (pin "1") (pinfunction "1_1") (pintype "passive"))
      (node (ref "R6") (pin "2") (pinfunction "2_2") (pintype "passive"))
    )
    (net (code "25") (name "Net-(R11-Pad2)") (class "Default")
      (node (ref "R11") (pin "2") (pinfunction "2_2") (pintype "passive"))
      (node (ref "R4") (pin "1") (pinfunction "1_1") (pintype "passive"))
    )
    (net (code "26") (name "Net-(R14-Pad2)") (class "Default")
      (node (ref "R14") (pin "2") (pinfunction "2_2") (pintype "passive"))
      (node (ref "R5") (pin "1") (pinfunction "1_1") (pintype "passive"))
    )
    (net (code "27") (name "Net-(R15-Pad2)") (class "Default")
      (node (ref "R15") (pin "2") (pinfunction "2_2") (pintype "passive"))
      (node (ref "R6") (pin "1") (pinfunction "1_1") (pintype "passive"))
    )
    (net (code "28") (name "Net-(R22-Pad1)") (class "Default")
      (node (ref "R22") (pin "1") (pinfunction "1_1") (pintype "passive"))
      (node (ref "R25") (pin "2") (pinfunction "2_2") (pintype "passive"))
    )
    (net (code "29") (name "Net-(R23-Pad1)") (class "Default")
      (node (ref "R23") (pin "1") (pinfunction "1_1") (pintype "passive"))
      (node (ref "R26") (pin "2") (pinfunction "2_2") (pintype "passive"))
    )
    (net (code "30") (name "Net-(R24-Pad1)") (class "Default")
      (node (ref "R24") (pin "1") (pinfunction "1_1") (pintype "passive"))
      (node (ref "R27") (pin "2") (pinfunction "2_2") (pintype "passive"))
    )
    (net (code "31") (name "Net-(R25-Pad1)") (class "Default")
      (node (ref "R25") (pin "1") (pinfunction "1_1") (pintype "passive"))
      (node (ref "R28") (pin "2") (pinfunction "2_2") (pintype "passive"))
    )
    (net (code "32") (name "Net-(R26-Pad1)") (class "Default")
      (node (ref "R26") (pin "1") (pinfunction "1_1") (pintype "passive"))
      (node (ref "R29") (pin "2") (pinfunction "2_2") (pintype "passive"))
    )
    (net (code "33") (name "Net-(R27-Pad1)") (class "Default")
      (node (ref "R27") (pin "1") (pinfunction "1_1") (pintype "passive"))
      (node (ref "R30") (pin "2") (pinfunction "2_2") (pintype "passive"))
    )
    (net (code "34") (name "Net-(TP14-G9)") (class "Default")
      (node (ref "C21") (pin "2") (pinfunction "2_2") (pintype "passive"))
      (node (ref "R28") (pin "1") (pinfunction "1_1") (pintype "passive"))
      (node (ref "R34") (pin "2") (pinfunction "2_2") (pintype "passive"))
      (node (ref "TP14") (pin "1") (pinfunction "G9_1") (pintype "passive"))
      (node (ref "U2") (pin "3") (pinfunction "VIN+_3") (pintype "input"))
      (node (ref "VD1") (pin "2") (pinfunction "C_2") (pintype "passive"))
      (node (ref "VD4") (pin "1") (pinfunction "C_1") (pintype "passive"))
    )
    (net (code "35") (name "Net-(TP15-G9)") (class "Default")
      (node (ref "C23") (pin "2") (pinfunction "2_2") (pintype "passive"))
      (node (ref "R29") (pin "1") (pinfunction "1_1") (pintype "passive"))
      (node (ref "R36") (pin "2") (pinfunction "2_2") (pintype "passive"))
      (node (ref "TP15") (pin "1") (pinfunction "G9_1") (pintype "passive"))
      (node (ref "U3") (pin "3") (pinfunction "VIN+_3") (pintype "input"))
      (node (ref "VD2") (pin "2") (pinfunction "C_2") (pintype "passive"))
      (node (ref "VD5") (pin "1") (pinfunction "C_1") (pintype "passive"))
    )
    (net (code "36") (name "Net-(TP16-G9)") (class "Default")
      (node (ref "C24") (pin "2") (pinfunction "2_2") (pintype "passive"))
      (node (ref "R30") (pin "1") (pinfunction "1_1") (pintype "passive"))
      (node (ref "R37") (pin "2") (pinfunction "2_2") (pintype "passive"))
      (node (ref "TP16") (pin "1") (pinfunction "G9_1") (pintype "passive"))
      (node (ref "U4") (pin "3") (pinfunction "VIN+_3") (pintype "input"))
      (node (ref "VD3") (pin "2") (pinfunction "C_2") (pintype "passive"))
      (node (ref "VD6") (pin "1") (pinfunction "C_1") (pintype "passive"))
    )
    (net (code "37") (name "Net-(TP20-G9)") (class "Default")
      (node (ref "L9") (pin "1") (pinfunction "1_1") (pintype "passive"))
      (node (ref "TP20") (pin "1") (pinfunction "G9_1") (pintype "passive"))
      (node (ref "TP9") (pin "1") (pinfunction "G9_1") (pintype "passive"))
    )
    (net (code "38") (name "Net-(U2-VOUT)") (class "Default")
      (node (ref "R31") (pin "2") (pinfunction "2_2") (pintype "passive"))
      (node (ref "U2") (pin "1") (pinfunction "VOUT_1") (pintype "output"))
    )
    (net (code "39") (name "Net-(U3-VOUT)") (class "Default")
      (node (ref "R32") (pin "2") (pinfunction "2_2") (pintype "passive"))
      (node (ref "U3") (pin "1") (pinfunction "VOUT_1") (pintype "output"))
    )
    (net (code "40") (name "Net-(U4-VOUT)") (class "Default")
      (node (ref "R33") (pin "2") (pinfunction "2_2") (pintype "passive"))
      (node (ref "U4") (pin "1") (pinfunction "VOUT_1") (pintype "output"))
    )
    (net (code "41") (name "Net-(VD10-C)") (class "Default")
      (node (ref "J1") (pin "2") (pinfunction "2_2") (pintype "passive"))
      (node (ref "VD10") (pin "1") (pinfunction "C_1") (pintype "passive"))
      (node (ref "VD11") (pin "1") (pinfunction "C_1") (pintype "passive"))
      (node (ref "VD12") (pin "1") (pinfunction "C_1") (pintype "passive"))
    )
  )
)
